# fsr_electrode_v2_0.net
KiCad netlist of a schematic drawn in EAGLE
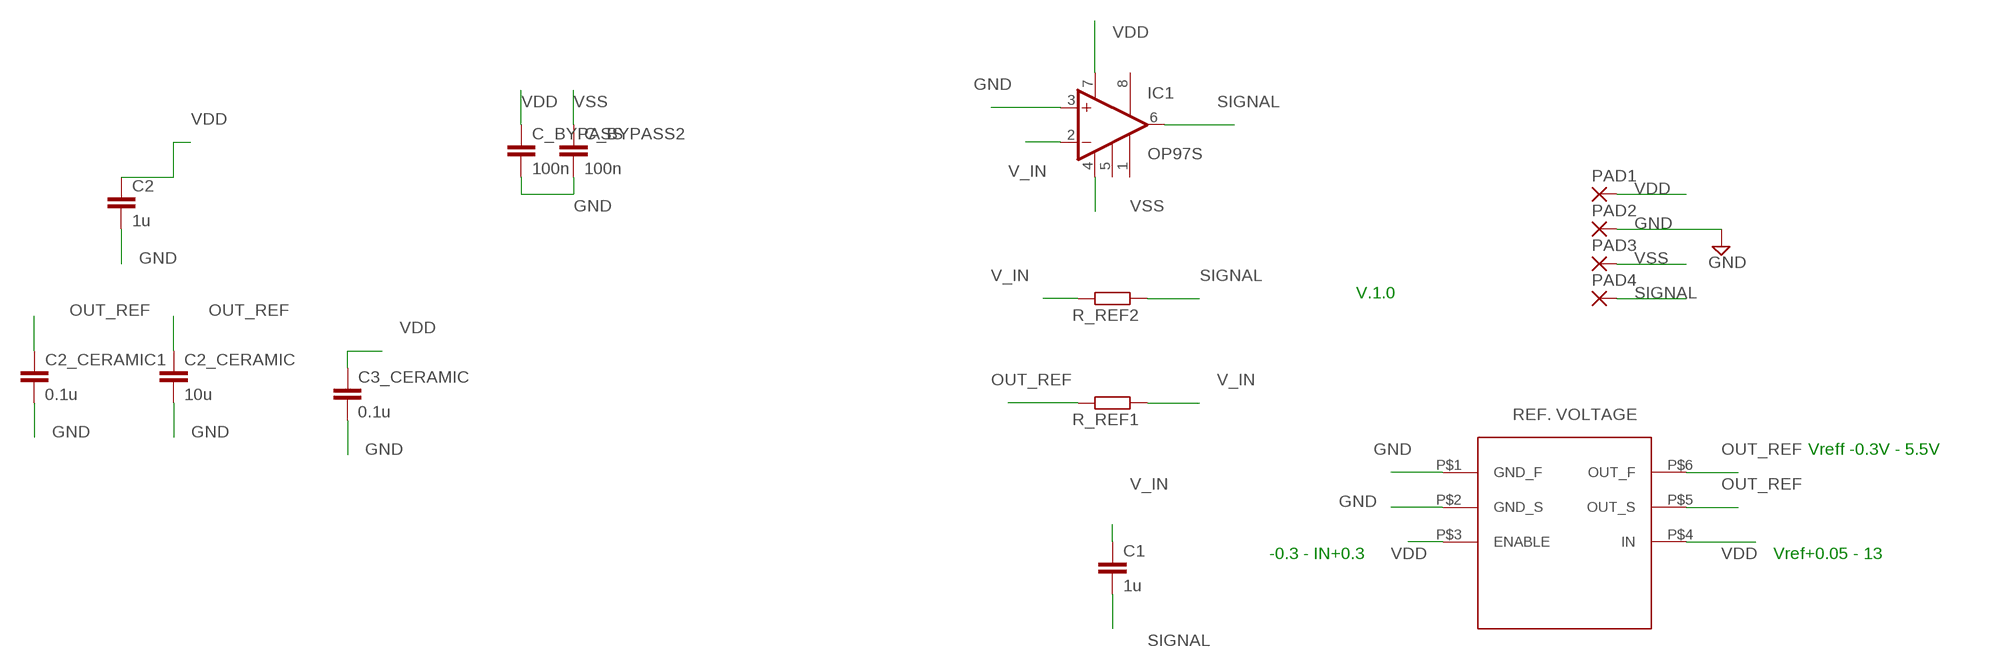
[diagram p0: schematic, sheet 1]

(export (version "E")
  (design (tool "Eeschema 10.0.6"))
  (components
    (comp (ref "C1")
      (value "1u")
      (footprint "eagle-import:C0805")
      (libsource (lib "eagle-import") (part "C-EUC0805"))
    )
    (comp (ref "C2")
      (value "1u")
      (footprint "eagle-import:C0805")
      (libsource (lib "eagle-import") (part "C-EUC0805"))
    )
    (comp (ref "C2_CERAMIC")
      (value "10u")
      (footprint "eagle-import:C0805")
      (libsource (lib "eagle-import") (part "C-EUC0805"))
    )
    (comp (ref "C2_CERAMIC1")
      (value "0.1u")
      (footprint "eagle-import:C0805")
      (libsource (lib "eagle-import") (part "C-EUC0805"))
    )
    (comp (ref "C3_CERAMIC")
      (value "0.1u")
      (footprint "eagle-import:C0805")
      (libsource (lib "eagle-import") (part "C-EUC0805"))
    )
    (comp (ref "C_BYPASS")
      (value "100n")
      (footprint "eagle-import:C0805")
      (libsource (lib "eagle-import") (part "resistor_348_C-EUC0805"))
    )
    (comp (ref "C_BYPASS2")
      (value "100n")
      (footprint "eagle-import:C0805")
      (libsource (lib "eagle-import") (part "resistor_348_C-EUC0805"))
    )
    (comp (ref "IC1")
      (value "OP97S")
      (footprint "eagle-import:SO08")
      (libsource (lib "eagle-import") (part "OP97S"))
    )
    (comp (ref "PAD1")
      (value "SMD5")
      (footprint "eagle-import:SMD2,54-5,08")
      (libsource (lib "eagle-import") (part "SMD5"))
    )
    (comp (ref "PAD2")
      (value "SMD5")
      (footprint "eagle-import:SMD2,54-5,08")
      (libsource (lib "eagle-import") (part "SMD5"))
    )
    (comp (ref "PAD3")
      (value "SMD5")
      (footprint "eagle-import:SMD2,54-5,08")
      (libsource (lib "eagle-import") (part "SMD5"))
    )
    (comp (ref "PAD4")
      (value "SMD5")
      (footprint "eagle-import:SMD2,54-5,08")
      (libsource (lib "eagle-import") (part "SMD5"))
    )
    (comp (ref "REF3450")
      (value "REF3450IDBVR")
      (footprint "eagle-import:UZUN")
      (libsource (lib "eagle-import") (part "REF3450IDBVR"))
    )
    (comp (ref "R_REF1")
      (value "10k")
      (footprint "eagle-import:M0805")
      (libsource (lib "eagle-import") (part "R-EU_M0805"))
    )
    (comp (ref "R_REF2")
      (value "10k")
      (footprint "eagle-import:M0805")
      (libsource (lib "eagle-import") (part "R-EU_M0805"))
    )
  )
  (nets
    (net (code "1") (name "/OUT_REF") (class "Default")
      (node (ref "C2_CERAMIC") (pin "1") (pinfunction "1_1") (pintype "passive"))
      (node (ref "C2_CERAMIC1") (pin "1") (pinfunction "1_1") (pintype "passive"))
      (node (ref "REF3450") (pin "P$5") (pinfunction "OUT_S_P$5") (pintype "bidirectional"))
      (node (ref "REF3450") (pin "P$6") (pinfunction "OUT_F_P$6") (pintype "bidirectional"))
      (node (ref "R_REF1") (pin "2") (pinfunction "2_2") (pintype "passive"))
    )
    (net (code "2") (name "/SIGNAL") (class "Default")
      (node (ref "C1") (pin "2") (pinfunction "2_2") (pintype "passive"))
      (node (ref "IC1") (pin "6") (pinfunction "OUT_6") (pintype "output"))
      (node (ref "PAD4") (pin "1") (pinfunction "P_1") (pintype "passive"))
      (node (ref "R_REF2") (pin "1") (pinfunction "1_1") (pintype "passive"))
    )
    (net (code "3") (name "/VDD") (class "Default")
      (node (ref "C2") (pin "1") (pinfunction "1_1") (pintype "passive"))
      (node (ref "C3_CERAMIC") (pin "1") (pinfunction "1_1") (pintype "passive"))
      (node (ref "C_BYPASS") (pin "1") (pinfunction "1_1") (pintype "passive"))
      (node (ref "IC1") (pin "7") (pinfunction "V+_7") (pintype "power_in"))
      (node (ref "PAD1") (pin "1") (pinfunction "P_1") (pintype "passive"))
      (node (ref "REF3450") (pin "P$3") (pinfunction "ENABLE_P$3") (pintype "bidirectional"))
      (node (ref "REF3450") (pin "P$4") (pinfunction "IN_P$4") (pintype "bidirectional"))
    )
    (net (code "4") (name "/VSS") (class "Default")
      (node (ref "C_BYPASS2") (pin "1") (pinfunction "1_1") (pintype "passive"))
      (node (ref "IC1") (pin "4") (pinfunction "V-_4") (pintype "power_in"))
      (node (ref "PAD3") (pin "1") (pinfunction "P_1") (pintype "passive"))
    )
    (net (code "5") (name "/V_IN") (class "Default")
      (node (ref "C1") (pin "1") (pinfunction "1_1") (pintype "passive"))
      (node (ref "IC1") (pin "2") (pinfunction "-IN_2") (pintype "input"))
      (node (ref "R_REF1") (pin "1") (pinfunction "1_1") (pintype "passive"))
      (node (ref "R_REF2") (pin "2") (pinfunction "2_2") (pintype "passive"))
    )
    (net (code "6") (name "GND") (class "Default")
      (node (ref "C2") (pin "2") (pinfunction "2_2") (pintype "passive"))
      (node (ref "C2_CERAMIC") (pin "2") (pinfunction "2_2") (pintype "passive"))
      (node (ref "C2_CERAMIC1") (pin "2") (pinfunction "2_2") (pintype "passive"))
      (node (ref "C3_CERAMIC") (pin "2") (pinfunction "2_2") (pintype "passive"))
      (node (ref "C_BYPASS") (pin "2") (pinfunction "2_2") (pintype "passive"))
      (node (ref "C_BYPASS2") (pin "2") (pinfunction "2_2") (pintype "passive"))
      (node (ref "IC1") (pin "3") (pinfunction "+IN_3") (pintype "input"))
      (node (ref "PAD2") (pin "1") (pinfunction "P_1") (pintype "passive"))
      (node (ref "REF3450") (pin "P$1") (pinfunction "GND_F_P$1") (pintype "bidirectional"))
      (node (ref "REF3450") (pin "P$2") (pinfunction "GND_S_P$2") (pintype "bidirectional"))
    )
    (net (code "7") (name "unconnected-(IC1-BAL1-Pad1)") (class "Default")
      (node (ref "IC1") (pin "1") (pinfunction "BAL1_1") (pintype "passive"))
    )
    (net (code "8") (name "unconnected-(IC1-BAL2-Pad8)") (class "Default")
      (node (ref "IC1") (pin "8") (pinfunction "BAL2_8") (pintype "passive"))
    )
    (net (code "9") (name "unconnected-(IC1-COMP-Pad5)") (class "Default")
      (node (ref "IC1") (pin "5") (pinfunction "COMP_5") (pintype "passive"))
    )
  )
)
